# neopixel-controller.net
KiCad netlist of a schematic drawn in EAGLE
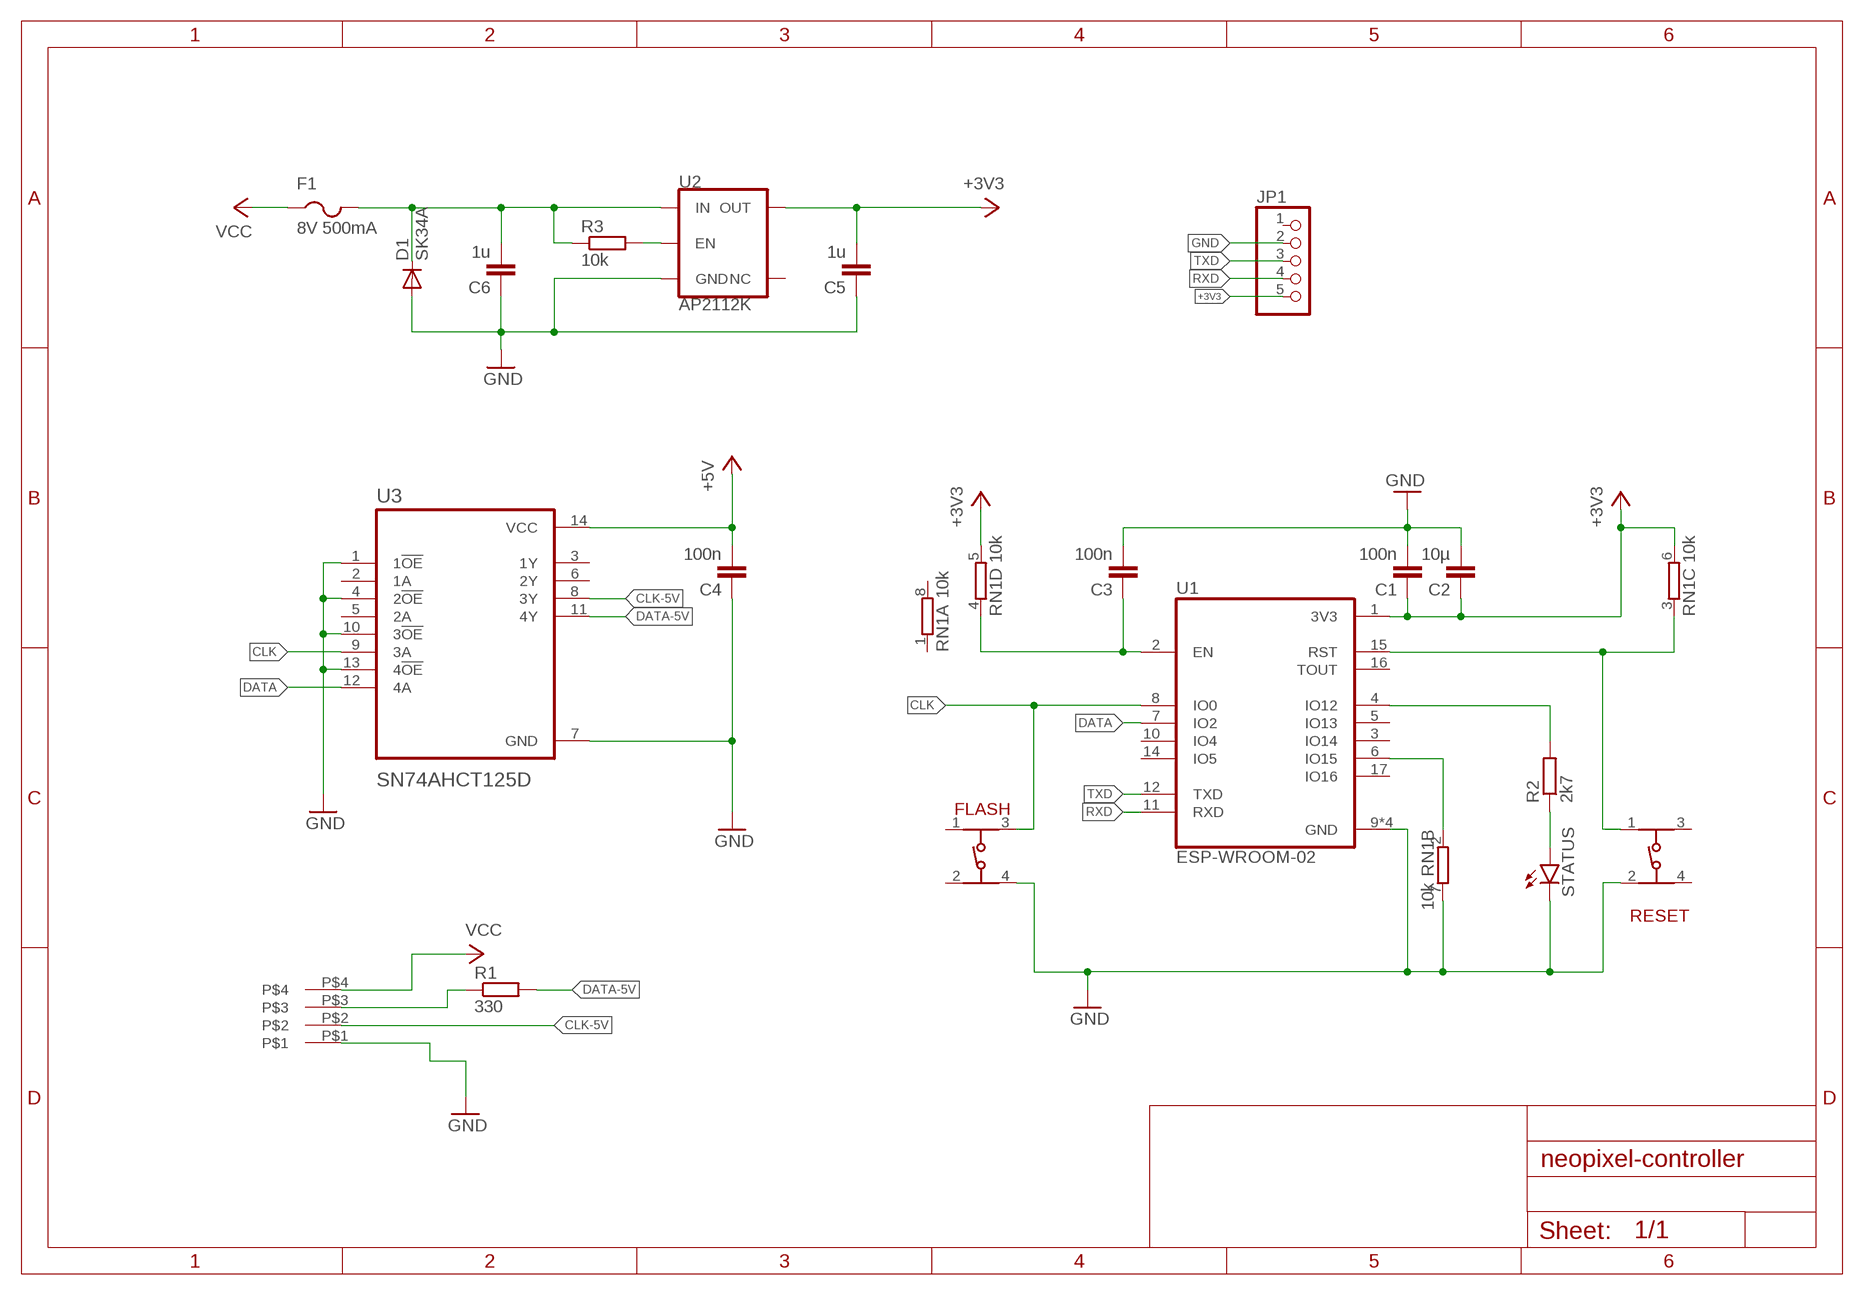
[diagram p0: schematic, sheet 1]

(export (version "E")
  (design (tool "Eeschema 10.0.6"))
  (components
    (comp (ref "C1")
      (value "100n")
      (footprint "eagle-import:C0805")
      (libsource (lib "eagle-import") (part "C-EUC0805"))
    )
    (comp (ref "C2")
      (value "10µ")
      (footprint "eagle-import:C0805")
      (libsource (lib "eagle-import") (part "C-EUC0805"))
    )
    (comp (ref "C3")
      (value "100n")
      (footprint "eagle-import:C0805")
      (libsource (lib "eagle-import") (part "C-EUC0805"))
    )
    (comp (ref "C4")
      (value "100n")
      (footprint "eagle-import:C0805")
      (libsource (lib "eagle-import") (part "C-EUC0805"))
    )
    (comp (ref "C5")
      (value "1u")
      (footprint "eagle-import:C0805")
      (libsource (lib "eagle-import") (part "C-EUC0805"))
    )
    (comp (ref "C6")
      (value "1u")
      (footprint "eagle-import:C0805")
      (libsource (lib "eagle-import") (part "C-EUC0805"))
    )
    (comp (ref "D1")
      (value "SK34A")
      (footprint "eagle-import:DO214AC")
      (libsource (lib "eagle-import") (part "DIODE-DO214AC"))
    )
    (comp (ref "F1")
      (value "8V 500mA")
      (footprint "eagle-import:R1206")
      (libsource (lib "eagle-import") (part "PTCFUSE-1206"))
    )
    (comp (ref "FLASH")
      (value "434153017835")
      (footprint "eagle-import:434153017835")
      (libsource (lib "eagle-import") (part "434153017835"))
    )
    (comp (ref "JP1")
      (value "PINHD-1X5")
      (footprint "eagle-import:1X05")
      (libsource (lib "eagle-import") (part "PINHD-1X5"))
    )
    (comp (ref "R1")
      (value "330")
      (footprint "eagle-import:R0805")
      (libsource (lib "eagle-import") (part "R-EU_R0805"))
    )
    (comp (ref "R2")
      (value "2k7")
      (footprint "eagle-import:R0805")
      (libsource (lib "eagle-import") (part "R-EU_R0805"))
    )
    (comp (ref "R3")
      (value "10k")
      (footprint "eagle-import:R0805")
      (libsource (lib "eagle-import") (part "R-EU_R0805"))
    )
    (comp (ref "RESET")
      (value "434153017835")
      (footprint "eagle-import:434153017835")
      (libsource (lib "eagle-import") (part "434153017835"))
    )
    (comp (ref "RN1")
      (value "10k")
      (footprint "eagle-import:EXB38V")
      (libsource (lib "eagle-import") (part "4R-NEXB38V"))
    )
    (comp (ref "STATUS")
      (value "LEDCHIPLED_0805")
      (footprint "eagle-import:CHIPLED_0805")
      (libsource (lib "eagle-import") (part "LEDCHIPLED_0805"))
    )
    (comp (ref "U$101")
      (value "MCV-1,5/4-G-3,81")
      (footprint "eagle-import:MCV-1,5_4-G-3,81")
      (libsource (lib "eagle-import") (part "MCV-1,5/4-G-3,81"))
    )
    (comp (ref "U1")
      (value "ESP-WROOM-02")
      (footprint "eagle-import:MODULE_ESP-WROOM-02")
      (fields (field (name "MF") "Espressif Systems"))
      (libsource (lib "eagle-import") (part "ESP-WROOM-02"))
    )
    (comp (ref "U2")
      (value "AP2112K")
      (footprint "eagle-import:SOT23-5")
      (libsource (lib "eagle-import") (part "V_REG_AP2112K-3.3V"))
    )
    (comp (ref "U3")
      (value "SN74AHCT125D")
      (footprint "eagle-import:SOIC127P600X175-14N")
      (fields (field (name "MF") "Texas Instruments"))
      (libsource (lib "eagle-import") (part "SN74AHCT125D"))
    )
  )
  (nets
    (net (code "1") (name "+3V3") (class "Default")
      (node (ref "C1") (pin "1") (pinfunction "1_1") (pintype "passive"))
      (node (ref "C2") (pin "1") (pinfunction "1_1") (pintype "passive"))
      (node (ref "C5") (pin "2") (pinfunction "2_2") (pintype "passive"))
      (node (ref "JP1") (pin "5") (pinfunction "5_5") (pintype "passive"))
      (node (ref "RN1") (pin "5") (pinfunction "2_5") (pintype "passive"))
      (node (ref "RN1") (pin "6") (pinfunction "2_6") (pintype "passive"))
      (node (ref "U1") (pin "1") (pinfunction "3V3_1") (pintype "power_in"))
      (node (ref "U2") (pin "5") (pinfunction "OUT_5") (pintype "passive"))
    )
    (net (code "2") (name "+5V") (class "Default")
      (node (ref "C4") (pin "2") (pinfunction "2_2") (pintype "passive"))
      (node (ref "C6") (pin "2") (pinfunction "2_2") (pintype "passive"))
      (node (ref "D1") (pin "C") (pinfunction "C_C") (pintype "passive"))
      (node (ref "F1") (pin "2") (pinfunction "2_2") (pintype "passive"))
      (node (ref "R3") (pin "1") (pinfunction "1_1") (pintype "passive"))
      (node (ref "U2") (pin "1") (pinfunction "IN_1") (pintype "input"))
      (node (ref "U3") (pin "14") (pinfunction "VCC_14") (pintype "power_in"))
    )
    (net (code "3") (name "CLK") (class "Default")
      (node (ref "FLASH") (pin "3") (pinfunction "2_3") (pintype "passive"))
      (node (ref "U1") (pin "8") (pinfunction "IO0_8") (pintype "bidirectional"))
      (node (ref "U3") (pin "9") (pinfunction "3A_9") (pintype "input"))
    )
    (net (code "4") (name "CLK-5V") (class "Default")
      (node (ref "U$101") (pin "P$2") (pinfunction "P$2_P$2") (pintype "bidirectional"))
      (node (ref "U3") (pin "8") (pinfunction "3Y_8") (pintype "output"))
    )
    (net (code "5") (name "DATA") (class "Default")
      (node (ref "U1") (pin "7") (pinfunction "IO2_7") (pintype "bidirectional"))
      (node (ref "U3") (pin "12") (pinfunction "4A_12") (pintype "input"))
    )
    (net (code "6") (name "DATA-5V") (class "Default")
      (node (ref "R1") (pin "2") (pinfunction "2_2") (pintype "passive"))
      (node (ref "U3") (pin "11") (pinfunction "4Y_11") (pintype "output"))
    )
    (net (code "7") (name "GND") (class "Default")
      (node (ref "C1") (pin "2") (pinfunction "2_2") (pintype "passive"))
      (node (ref "C2") (pin "2") (pinfunction "2_2") (pintype "passive"))
      (node (ref "C3") (pin "2") (pinfunction "2_2") (pintype "passive"))
      (node (ref "C4") (pin "1") (pinfunction "1_1") (pintype "passive"))
      (node (ref "C5") (pin "1") (pinfunction "1_1") (pintype "passive"))
      (node (ref "C6") (pin "1") (pinfunction "1_1") (pintype "passive"))
      (node (ref "D1") (pin "A") (pinfunction "A_A") (pintype "passive"))
      (node (ref "FLASH") (pin "4") (pinfunction "4_4") (pintype "passive"))
      (node (ref "JP1") (pin "2") (pinfunction "2_2") (pintype "passive"))
      (node (ref "RESET") (pin "2") (pinfunction "3_2") (pintype "passive"))
      (node (ref "RN1") (pin "7") (pinfunction "2_7") (pintype "passive"))
      (node (ref "STATUS") (pin "C") (pinfunction "C_C") (pintype "passive"))
      (node (ref "U$101") (pin "P$1") (pinfunction "P$1_P$1") (pintype "bidirectional"))
      (node (ref "U1") (pin "13") (pinfunction "GND_13") (pintype "power_in"))
      (node (ref "U1") (pin "18") (pinfunction "GND_18") (pintype "power_in"))
      (node (ref "U1") (pin "19") (pinfunction "GND_19") (pintype "power_in"))
      (node (ref "U1") (pin "9") (pinfunction "GND_9") (pintype "power_in"))
      (node (ref "U2") (pin "2") (pinfunction "GND_2") (pintype "input"))
      (node (ref "U3") (pin "1") (pinfunction "1~{OE}_1") (pintype "input"))
      (node (ref "U3") (pin "10") (pinfunction "3~{OE}_10") (pintype "input"))
      (node (ref "U3") (pin "13") (pinfunction "4~{OE}_13") (pintype "input"))
      (node (ref "U3") (pin "4") (pinfunction "2~{OE}_4") (pintype "input"))
      (node (ref "U3") (pin "7") (pinfunction "GND_7") (pintype "power_in"))
    )
    (net (code "8") (name "Net-(R1-Pad1)") (class "Default")
      (node (ref "R1") (pin "1") (pinfunction "1_1") (pintype "passive"))
      (node (ref "U$101") (pin "P$3") (pinfunction "P$3_P$3") (pintype "bidirectional"))
    )
    (net (code "9") (name "Net-(R2-Pad1)") (class "Default")
      (node (ref "R2") (pin "1") (pinfunction "1_1") (pintype "passive"))
      (node (ref "STATUS") (pin "A") (pinfunction "A_A") (pintype "passive"))
    )
    (net (code "10") (name "Net-(RN1B-1)") (class "Default")
      (node (ref "RN1") (pin "2") (pinfunction "1_2") (pintype "passive"))
      (node (ref "U1") (pin "6") (pinfunction "IO15_6") (pintype "bidirectional"))
    )
    (net (code "11") (name "Net-(RN1C-1)") (class "Default")
      (node (ref "RESET") (pin "1") (pinfunction "1_1") (pintype "passive"))
      (node (ref "RN1") (pin "3") (pinfunction "1_3") (pintype "passive"))
      (node (ref "U1") (pin "15") (pinfunction "RST_15") (pintype "bidirectional"))
    )
    (net (code "12") (name "Net-(RN1D-1)") (class "Default")
      (node (ref "C3") (pin "1") (pinfunction "1_1") (pintype "passive"))
      (node (ref "RN1") (pin "4") (pinfunction "1_4") (pintype "passive"))
      (node (ref "U1") (pin "2") (pinfunction "EN_2") (pintype "input"))
    )
    (net (code "13") (name "Net-(U1-IO12)") (class "Default")
      (node (ref "R2") (pin "2") (pinfunction "2_2") (pintype "passive"))
      (node (ref "U1") (pin "4") (pinfunction "IO12_4") (pintype "bidirectional"))
    )
    (net (code "14") (name "Net-(U2-EN)") (class "Default")
      (node (ref "R3") (pin "2") (pinfunction "2_2") (pintype "passive"))
      (node (ref "U2") (pin "3") (pinfunction "EN_3") (pintype "input"))
    )
    (net (code "15") (name "RXD") (class "Default")
      (node (ref "JP1") (pin "4") (pinfunction "4_4") (pintype "passive"))
      (node (ref "U1") (pin "11") (pinfunction "RXD_11") (pintype "bidirectional"))
    )
    (net (code "16") (name "TXD") (class "Default")
      (node (ref "JP1") (pin "3") (pinfunction "3_3") (pintype "passive"))
      (node (ref "U1") (pin "12") (pinfunction "TXD_12") (pintype "bidirectional"))
    )
    (net (code "17") (name "VCC") (class "Default")
      (node (ref "F1") (pin "1") (pinfunction "1_1") (pintype "passive"))
      (node (ref "U$101") (pin "P$4") (pinfunction "P$4_P$4") (pintype "bidirectional"))
    )
    (net (code "18") (name "unconnected-(FLASH-3-Pad2)") (class "Default")
      (node (ref "FLASH") (pin "2") (pinfunction "3_2") (pintype "passive"))
    )
    (net (code "19") (name "unconnected-(FLASH-Pad1)") (class "Default")
      (node (ref "FLASH") (pin "1") (pinfunction "1_1") (pintype "passive"))
    )
    (net (code "20") (name "unconnected-(JP1-Pad1)") (class "Default")
      (node (ref "JP1") (pin "1") (pinfunction "1_1") (pintype "passive"))
    )
    (net (code "21") (name "unconnected-(RESET-2-Pad3)") (class "Default")
      (node (ref "RESET") (pin "3") (pinfunction "2_3") (pintype "passive"))
    )
    (net (code "22") (name "unconnected-(RESET-Pad4)") (class "Default")
      (node (ref "RESET") (pin "4") (pinfunction "4_4") (pintype "passive"))
    )
    (net (code "23") (name "unconnected-(RN1-Pad1)") (class "Default")
      (node (ref "RN1") (pin "1") (pinfunction "1_1") (pintype "passive"))
    )
    (net (code "24") (name "unconnected-(RN1A-2-Pad8)") (class "Default")
      (node (ref "RN1") (pin "8") (pinfunction "2_8") (pintype "passive"))
    )
    (net (code "25") (name "unconnected-(U1-IO4-Pad10)") (class "Default")
      (node (ref "U1") (pin "10") (pinfunction "IO4_10") (pintype "bidirectional"))
    )
    (net (code "26") (name "unconnected-(U1-IO5-Pad14)") (class "Default")
      (node (ref "U1") (pin "14") (pinfunction "IO5_14") (pintype "open_collector"))
    )
    (net (code "27") (name "unconnected-(U1-IO13-Pad5)") (class "Default")
      (node (ref "U1") (pin "5") (pinfunction "IO13_5") (pintype "bidirectional"))
    )
    (net (code "28") (name "unconnected-(U1-IO14-Pad3)") (class "Default")
      (node (ref "U1") (pin "3") (pinfunction "IO14_3") (pintype "bidirectional"))
    )
    (net (code "29") (name "unconnected-(U1-IO16-Pad17)") (class "Default")
      (node (ref "U1") (pin "17") (pinfunction "IO16_17") (pintype "bidirectional"))
    )
    (net (code "30") (name "unconnected-(U1-TOUT-Pad16)") (class "Default")
      (node (ref "U1") (pin "16") (pinfunction "TOUT_16") (pintype "bidirectional"))
    )
    (net (code "31") (name "unconnected-(U2-NC-Pad4)") (class "Default")
      (node (ref "U2") (pin "4") (pinfunction "NC_4") (pintype "no_connect"))
    )
    (net (code "32") (name "unconnected-(U3-1A-Pad2)") (class "Default")
      (node (ref "U3") (pin "2") (pinfunction "1A_2") (pintype "input"))
    )
    (net (code "33") (name "unconnected-(U3-1Y-Pad3)") (class "Default")
      (node (ref "U3") (pin "3") (pinfunction "1Y_3") (pintype "output"))
    )
    (net (code "34") (name "unconnected-(U3-2A-Pad5)") (class "Default")
      (node (ref "U3") (pin "5") (pinfunction "2A_5") (pintype "input"))
    )
    (net (code "35") (name "unconnected-(U3-2Y-Pad6)") (class "Default")
      (node (ref "U3") (pin "6") (pinfunction "2Y_6") (pintype "output"))
    )
  )
)
